# I2C.net
KiCad netlist of a schematic drawn in Altium Designer
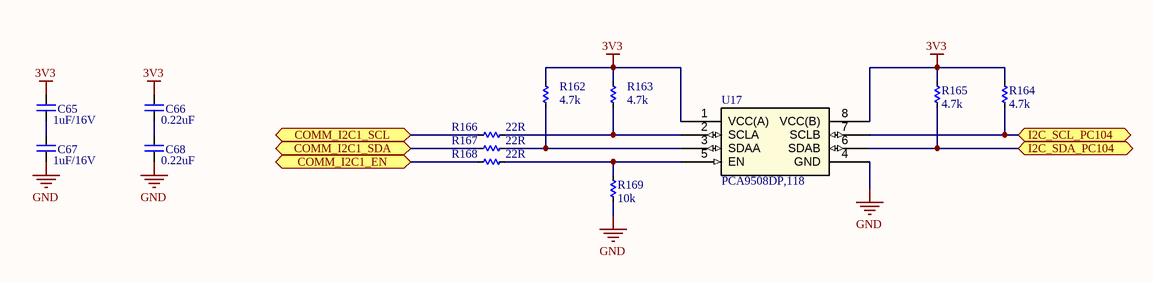
[diagram p0: I2C.SchDoc]

(export (version "E")
  (design (tool "Eeschema 10.0.6"))
  (components
    (comp (ref "C65")
      (value "1uF/16V")
      (footprint "CAP_C_1608X80")
      (description "CAP_Chip")
      (libsource (lib "LABLIB") (part "CAP_SMD"))
    )
    (comp (ref "C66")
      (value "0.22uF")
      (footprint "CAP_C_1608X80")
      (description "CAP_Chip")
      (libsource (lib "LABLIB") (part "CAP_SMD"))
    )
    (comp (ref "C67")
      (value "1uF/16V")
      (footprint "CAP_C_1608X80")
      (description "CAP_Chip")
      (libsource (lib "LABLIB") (part "CAP_SMD"))
    )
    (comp (ref "C68")
      (value "0.22uF")
      (footprint "CAP_C_1608X80")
      (description "CAP_Chip")
      (libsource (lib "LABLIB") (part "CAP_SMD"))
    )
    (comp (ref "R162")
      (value "4.7k")
      (footprint "RES_C_1608X60")
      (description "RES")
      (libsource (lib "LABLIB") (part "_RES_B_2"))
    )
    (comp (ref "R163")
      (value "4.7k")
      (footprint "RES_C_1608X60")
      (description "RES")
      (libsource (lib "LABLIB") (part "_RES_B_2"))
    )
    (comp (ref "R164")
      (value "4.7k")
      (footprint "RES_C_1608X60")
      (description "RES")
      (libsource (lib "LABLIB") (part "_RES_B_2"))
    )
    (comp (ref "R165")
      (value "4.7k")
      (footprint "RES_C_1608X60")
      (description "RES")
      (libsource (lib "LABLIB") (part "_RES_B_2"))
    )
    (comp (ref "R166")
      (value "22R")
      (footprint "RES_C_1608X60")
      (description "RES")
      (libsource (lib "LABLIB") (part "_RES_B_2"))
    )
    (comp (ref "R167")
      (value "22R")
      (footprint "RES_C_1608X60")
      (description "RES")
      (libsource (lib "LABLIB") (part "_RES_B_2"))
    )
    (comp (ref "R168")
      (value "22R")
      (footprint "RES_C_1608X60")
      (description "RES")
      (libsource (lib "LABLIB") (part "_RES_B_2"))
    )
    (comp (ref "R169")
      (value "10k")
      (footprint "RES_C_1608X60")
      (description "RES")
      (libsource (lib "LABLIB") (part "_RES_B_2"))
    )
    (comp (ref "U17")
      (value "PCA9508DP,118")
      (footprint "TSSOP8_SOT505-1_NXP")
      (description "No Description Available")
      (fields (field (name "COPYRIGHT") "Copyright (C) 2025 Ultra Librarian. All rights reserved."))
      (libsource (lib "COMM_SCHLIB") (part "PCA9508DP,118"))
    )
  )
  (nets
    (net (code "1") (name "/COMM_I2C1_EN") (class "Default")
      (node (ref "R168") (pin "2") (pinfunction "2_2") (pintype "passive"))
    )
    (net (code "2") (name "/COMM_I2C1_SCL") (class "Default")
      (node (ref "R166") (pin "2") (pinfunction "2_2") (pintype "passive"))
    )
    (net (code "3") (name "/COMM_I2C1_SDA") (class "Default")
      (node (ref "R167") (pin "2") (pinfunction "2_2") (pintype "passive"))
    )
    (net (code "4") (name "/I2C_SCL_PC104") (class "Default")
      (node (ref "R164") (pin "2") (pinfunction "2_2") (pintype "passive"))
      (node (ref "U17") (pin "7") (pinfunction "SCLB_7") (pintype "bidirectional"))
    )
    (net (code "5") (name "/I2C_SDA_PC104") (class "Default")
      (node (ref "R165") (pin "2") (pinfunction "2_2") (pintype "passive"))
      (node (ref "U17") (pin "6") (pinfunction "SDAB_6") (pintype "bidirectional"))
    )
    (net (code "6") (name "3V3") (class "Default")
      (node (ref "C65") (pin "2") (pinfunction "2_2") (pintype "passive"))
      (node (ref "C66") (pin "2") (pinfunction "2_2") (pintype "passive"))
      (node (ref "R162") (pin "1") (pinfunction "1_1") (pintype "passive"))
      (node (ref "R163") (pin "1") (pinfunction "1_1") (pintype "passive"))
      (node (ref "R164") (pin "1") (pinfunction "1_1") (pintype "passive"))
      (node (ref "R165") (pin "1") (pinfunction "1_1") (pintype "passive"))
      (node (ref "U17") (pin "1") (pinfunction "VCC(A)_1") (pintype "power_in"))
      (node (ref "U17") (pin "8") (pinfunction "VCC(B)_8") (pintype "power_in"))
    )
    (net (code "7") (name "GND") (class "Default")
      (node (ref "C67") (pin "1") (pinfunction "1_1") (pintype "passive"))
      (node (ref "C68") (pin "1") (pinfunction "1_1") (pintype "passive"))
      (node (ref "R169") (pin "2") (pinfunction "2_2") (pintype "passive"))
      (node (ref "U17") (pin "4") (pinfunction "GND_4") (pintype "power_in"))
    )
    (net (code "8") (name "Net-(C65-Pad1)") (class "Default")
      (node (ref "C65") (pin "1") (pinfunction "1_1") (pintype "passive"))
      (node (ref "C67") (pin "2") (pinfunction "2_2") (pintype "passive"))
    )
    (net (code "9") (name "Net-(C66-Pad1)") (class "Default")
      (node (ref "C66") (pin "1") (pinfunction "1_1") (pintype "passive"))
      (node (ref "C68") (pin "2") (pinfunction "2_2") (pintype "passive"))
    )
    (net (code "10") (name "Net-(U17-EN)") (class "Default")
      (node (ref "R168") (pin "1") (pinfunction "1_1") (pintype "passive"))
      (node (ref "R169") (pin "1") (pinfunction "1_1") (pintype "passive"))
      (node (ref "U17") (pin "5") (pinfunction "EN_5") (pintype "input"))
    )
    (net (code "11") (name "Net-(U17-SCLA)") (class "Default")
      (node (ref "R163") (pin "2") (pinfunction "2_2") (pintype "passive"))
      (node (ref "R166") (pin "1") (pinfunction "1_1") (pintype "passive"))
      (node (ref "U17") (pin "2") (pinfunction "SCLA_2") (pintype "bidirectional"))
    )
    (net (code "12") (name "Net-(U17-SDAA)") (class "Default")
      (node (ref "R162") (pin "2") (pinfunction "2_2") (pintype "passive"))
      (node (ref "R167") (pin "1") (pinfunction "1_1") (pintype "passive"))
      (node (ref "U17") (pin "3") (pinfunction "SDAA_3") (pintype "bidirectional"))
    )
  )
)
